# T2E.net
KiCad netlist of a schematic drawn in EAGLE
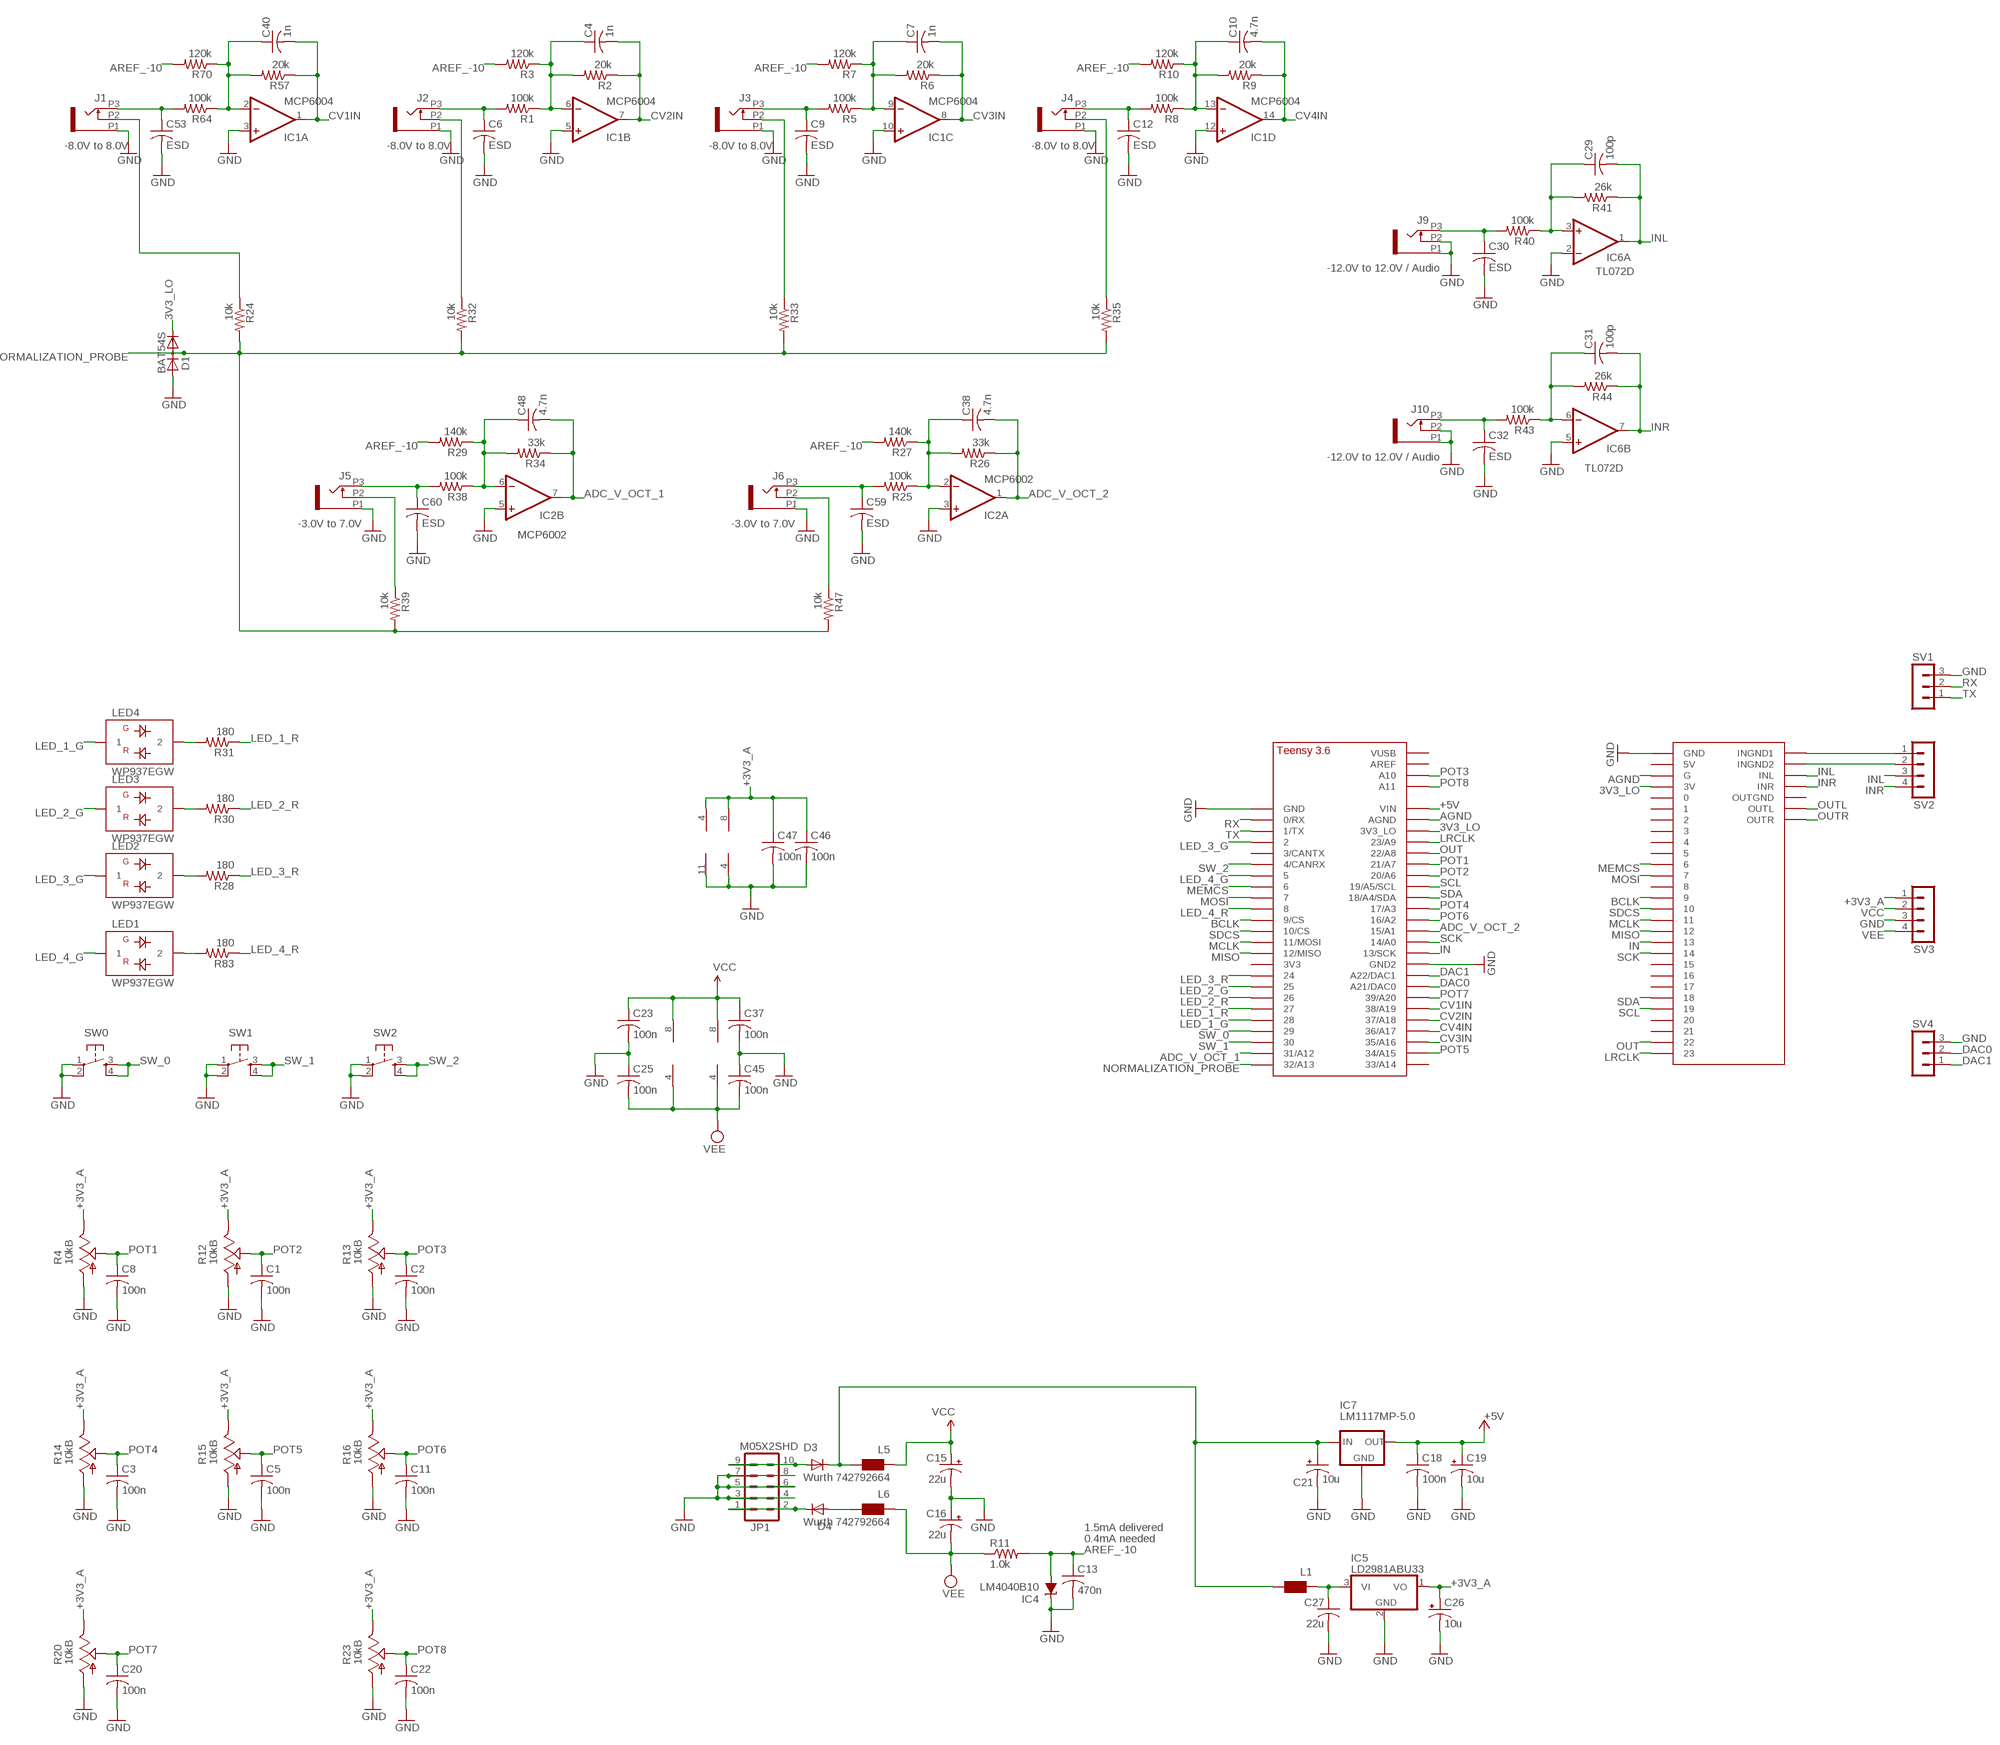
[diagram p0: schematic, sheet 1, part 1 of 2]
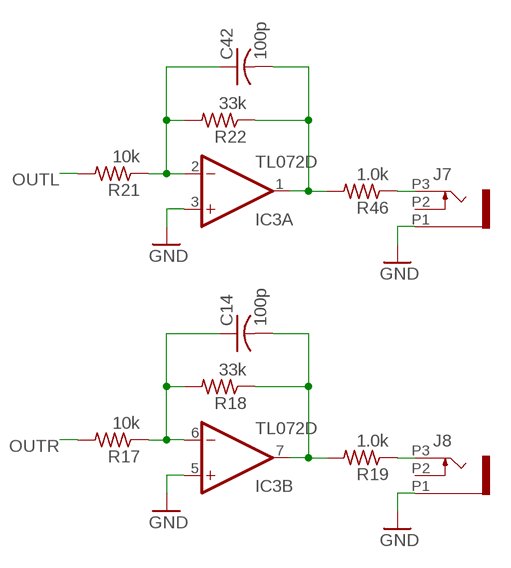
[diagram p1: schematic, sheet 1, part 2 of 2]

(export (version "E")
  (design (tool "Eeschema 10.0.6"))
  (components
    (comp (ref "C1")
      (value "100n")
      (footprint "eagle-import:C0603")
      (libsource (lib "eagle-import") (part "C-USC0603"))
    )
    (comp (ref "C2")
      (value "100n")
      (footprint "eagle-import:C0603")
      (libsource (lib "eagle-import") (part "C-USC0603"))
    )
    (comp (ref "C3")
      (value "100n")
      (footprint "eagle-import:C0603")
      (libsource (lib "eagle-import") (part "C-USC0603"))
    )
    (comp (ref "C4")
      (value "1n")
      (footprint "eagle-import:C0603")
      (libsource (lib "eagle-import") (part "C-USC0603"))
    )
    (comp (ref "C5")
      (value "100n")
      (footprint "eagle-import:C0603")
      (libsource (lib "eagle-import") (part "C-USC0603"))
    )
    (comp (ref "C6")
      (value "ESD")
      (footprint "eagle-import:C0603")
      (libsource (lib "eagle-import") (part "C-USC0603"))
    )
    (comp (ref "C7")
      (value "1n")
      (footprint "eagle-import:C0603")
      (libsource (lib "eagle-import") (part "C-USC0603"))
    )
    (comp (ref "C8")
      (value "100n")
      (footprint "eagle-import:C0603")
      (libsource (lib "eagle-import") (part "C-USC0603"))
    )
    (comp (ref "C9")
      (value "ESD")
      (footprint "eagle-import:C0603")
      (libsource (lib "eagle-import") (part "C-USC0603"))
    )
    (comp (ref "C10")
      (value "4.7n")
      (footprint "eagle-import:C0603")
      (libsource (lib "eagle-import") (part "C-USC0603"))
    )
    (comp (ref "C11")
      (value "100n")
      (footprint "eagle-import:C0603")
      (libsource (lib "eagle-import") (part "C-USC0603"))
    )
    (comp (ref "C12")
      (value "ESD")
      (footprint "eagle-import:C0603")
      (libsource (lib "eagle-import") (part "C-USC0603"))
    )
    (comp (ref "C13")
      (value "470n")
      (footprint "eagle-import:C0603")
      (libsource (lib "eagle-import") (part "C-USC0603"))
    )
    (comp (ref "C14")
      (value "100p")
      (footprint "eagle-import:C0603")
      (libsource (lib "eagle-import") (part "C-USC0603"))
    )
    (comp (ref "C15")
      (value "22u")
      (footprint "eagle-import:PANASONIC_C")
      (libsource (lib "eagle-import") (part "CPOL-USC"))
    )
    (comp (ref "C16")
      (value "22u")
      (footprint "eagle-import:PANASONIC_C")
      (libsource (lib "eagle-import") (part "CPOL-USC"))
    )
    (comp (ref "C18")
      (value "100n")
      (footprint "eagle-import:C0603")
      (libsource (lib "eagle-import") (part "C-USC0603"))
    )
    (comp (ref "C19")
      (value "10u")
      (footprint "eagle-import:PANASONIC_C")
      (libsource (lib "eagle-import") (part "CPOL-USC"))
    )
    (comp (ref "C20")
      (value "100n")
      (footprint "eagle-import:C0603")
      (libsource (lib "eagle-import") (part "C-USC0603"))
    )
    (comp (ref "C21")
      (value "10u")
      (footprint "eagle-import:PANASONIC_C")
      (libsource (lib "eagle-import") (part "CPOL-USC"))
    )
    (comp (ref "C22")
      (value "100n")
      (footprint "eagle-import:C0603")
      (libsource (lib "eagle-import") (part "C-USC0603"))
    )
    (comp (ref "C23")
      (value "100n")
      (footprint "eagle-import:C0603")
      (libsource (lib "eagle-import") (part "C-USC0603"))
    )
    (comp (ref "C25")
      (value "100n")
      (footprint "eagle-import:C0603")
      (libsource (lib "eagle-import") (part "C-USC0603"))
    )
    (comp (ref "C26")
      (value "10u")
      (footprint "eagle-import:PANASONIC_A")
      (libsource (lib "eagle-import") (part "CPOL-USA"))
    )
    (comp (ref "C27")
      (value "22u")
      (footprint "eagle-import:C1206")
      (libsource (lib "eagle-import") (part "C-USC1206"))
    )
    (comp (ref "C29")
      (value "100p")
      (footprint "eagle-import:C0603")
      (libsource (lib "eagle-import") (part "C-USC0603"))
    )
    (comp (ref "C30")
      (value "ESD")
      (footprint "eagle-import:C0603")
      (libsource (lib "eagle-import") (part "C-USC0603"))
    )
    (comp (ref "C31")
      (value "100p")
      (footprint "eagle-import:C0603")
      (libsource (lib "eagle-import") (part "C-USC0603"))
    )
    (comp (ref "C32")
      (value "ESD")
      (footprint "eagle-import:C0603")
      (libsource (lib "eagle-import") (part "C-USC0603"))
    )
    (comp (ref "C37")
      (value "100n")
      (footprint "eagle-import:C0603")
      (libsource (lib "eagle-import") (part "C-USC0603"))
    )
    (comp (ref "C38")
      (value "4.7n")
      (footprint "eagle-import:C0603")
      (libsource (lib "eagle-import") (part "C-USC0603"))
    )
    (comp (ref "C40")
      (value "1n")
      (footprint "eagle-import:C0603")
      (libsource (lib "eagle-import") (part "C-USC0603"))
    )
    (comp (ref "C42")
      (value "100p")
      (footprint "eagle-import:C0603")
      (libsource (lib "eagle-import") (part "C-USC0603"))
    )
    (comp (ref "C45")
      (value "100n")
      (footprint "eagle-import:C0603")
      (libsource (lib "eagle-import") (part "C-USC0603"))
    )
    (comp (ref "C46")
      (value "100n")
      (footprint "eagle-import:C0603")
      (libsource (lib "eagle-import") (part "C-USC0603"))
    )
    (comp (ref "C47")
      (value "100n")
      (footprint "eagle-import:C0603")
      (libsource (lib "eagle-import") (part "C-USC0603"))
    )
    (comp (ref "C48")
      (value "4.7n")
      (footprint "eagle-import:C0603")
      (libsource (lib "eagle-import") (part "C-USC0603"))
    )
    (comp (ref "C53")
      (value "ESD")
      (footprint "eagle-import:C0603")
      (libsource (lib "eagle-import") (part "C-USC0603"))
    )
    (comp (ref "C59")
      (value "ESD")
      (footprint "eagle-import:C0603")
      (libsource (lib "eagle-import") (part "C-USC0603"))
    )
    (comp (ref "C60")
      (value "ESD")
      (footprint "eagle-import:C0603")
      (libsource (lib "eagle-import") (part "C-USC0603"))
    )
    (comp (ref "D1")
      (value "BAT54S")
      (footprint "eagle-import:SOT23")
      (libsource (lib "eagle-import") (part "DIODE_2CACA-SOT23"))
    )
    (comp (ref "D3")
      (value "1N5819HW")
      (footprint "eagle-import:SOD123")
      (libsource (lib "eagle-import") (part "DIODE-SOD123"))
    )
    (comp (ref "D4")
      (value "1N5819HW")
      (footprint "eagle-import:SOD123")
      (libsource (lib "eagle-import") (part "DIODE-SOD123"))
    )
    (comp (ref "IC1")
      (value "MCP6004")
      (footprint "eagle-import:SO14")
      (libsource (lib "eagle-import") (part "TL074D"))
    )
    (comp (ref "IC2")
      (value "MCP6002")
      (footprint "eagle-import:SO08")
      (libsource (lib "eagle-import") (part "TL072D"))
    )
    (comp (ref "IC3")
      (value "TL072D")
      (footprint "eagle-import:SO08")
      (libsource (lib "eagle-import") (part "TL072D"))
    )
    (comp (ref "IC4")
      (value "LM4040B10")
      (footprint "eagle-import:DBZ_R-PDSO-G3")
      (libsource (lib "eagle-import") (part "LM4041DBZB12"))
    )
    (comp (ref "IC5")
      (value "LD2981ABU33")
      (footprint "eagle-import:SOT89")
      (libsource (lib "eagle-import") (part "LD2981ABU"))
    )
    (comp (ref "IC6")
      (value "TL072D")
      (footprint "eagle-import:SO08")
      (libsource (lib "eagle-import") (part "TL072D"))
    )
    (comp (ref "IC7")
      (value "LM1117MP-5.0")
      (footprint "eagle-import:SOT223")
      (fields (field (name "MF") "Texas Instruments"))
      (libsource (lib "eagle-import") (part "LM1117?-MP5.0"))
    )
    (comp (ref "J1")
      (value "PJ301_THONKICONN6")
      (footprint "eagle-import:WQP_PJ_301M6")
      (libsource (lib "eagle-import") (part "PJ301_THONKICONN6"))
    )
    (comp (ref "J2")
      (value "PJ301_THONKICONN6")
      (footprint "eagle-import:WQP_PJ_301M6")
      (libsource (lib "eagle-import") (part "PJ301_THONKICONN6"))
    )
    (comp (ref "J3")
      (value "PJ301_THONKICONN6")
      (footprint "eagle-import:WQP_PJ_301M6")
      (libsource (lib "eagle-import") (part "PJ301_THONKICONN6"))
    )
    (comp (ref "J4")
      (value "PJ301_THONKICONN6")
      (footprint "eagle-import:WQP_PJ_301M6")
      (libsource (lib "eagle-import") (part "PJ301_THONKICONN6"))
    )
    (comp (ref "J5")
      (value "PJ301_THONKICONN6")
      (footprint "eagle-import:WQP_PJ_301M6")
      (libsource (lib "eagle-import") (part "og-pj301_variations_PJ301_THONKICONN6"))
    )
    (comp (ref "J6")
      (value "PJ301_THONKICONN6")
      (footprint "eagle-import:WQP_PJ_301M6")
      (libsource (lib "eagle-import") (part "og-pj301_variations_PJ301_THONKICONN6"))
    )
    (comp (ref "J7")
      (value "PJ301_THONKICONN6")
      (footprint "eagle-import:WQP_PJ_301M6")
      (libsource (lib "eagle-import") (part "og-pj301_variations_PJ301_THONKICONN6"))
    )
    (comp (ref "J8")
      (value "PJ301_THONKICONN6")
      (footprint "eagle-import:WQP_PJ_301M6")
      (libsource (lib "eagle-import") (part "og-pj301_variations_PJ301_THONKICONN6"))
    )
    (comp (ref "J9")
      (value "PJ301_THONKICONN6")
      (footprint "eagle-import:WQP_PJ_301M6")
      (libsource (lib "eagle-import") (part "PJ301_THONKICONN6"))
    )
    (comp (ref "J10")
      (value "PJ301_THONKICONN6")
      (footprint "eagle-import:WQP_PJ_301M6")
      (libsource (lib "eagle-import") (part "PJ301_THONKICONN6"))
    )
    (comp (ref "JP1")
      (value "M05X2SHD")
      (footprint "eagle-import:2X5-SHROUDED")
      (libsource (lib "eagle-import") (part "M05X2SHD"))
    )
    (comp (ref "L1")
      (value "WE-CBF_0603")
      (footprint "eagle-import:0603")
      (libsource (lib "eagle-import") (part "WE-CBF_0603"))
    )
    (comp (ref "L5")
      (value "Wurth 742792664")
      (footprint "eagle-import:0603")
      (libsource (lib "eagle-import") (part "WE-CBF_0603"))
    )
    (comp (ref "L6")
      (value "Wurth 742792664")
      (footprint "eagle-import:0603")
      (libsource (lib "eagle-import") (part "WE-CBF_0603"))
    )
    (comp (ref "LED1")
      (value "WP937EGW")
      (footprint "eagle-import:LED3MM")
      (libsource (lib "eagle-import") (part "LED-BICOLOR-SHARED-THROUGHHOLE"))
    )
    (comp (ref "LED2")
      (value "WP937EGW")
      (footprint "eagle-import:LED3MM")
      (libsource (lib "eagle-import") (part "LED-BICOLOR-SHARED-THROUGHHOLE"))
    )
    (comp (ref "LED3")
      (value "WP937EGW")
      (footprint "eagle-import:LED3MM")
      (libsource (lib "eagle-import") (part "LED-BICOLOR-SHARED-THROUGHHOLE"))
    )
    (comp (ref "LED4")
      (value "WP937EGW")
      (footprint "eagle-import:LED3MM")
      (libsource (lib "eagle-import") (part "LED-BICOLOR-SHARED-THROUGHHOLE"))
    )
    (comp (ref "R1")
      (value "100k")
      (footprint "eagle-import:R0603")
      (libsource (lib "eagle-import") (part "R-US_R0603"))
    )
    (comp (ref "R2")
      (value "20k")
      (footprint "eagle-import:R0603")
      (libsource (lib "eagle-import") (part "R-US_R0603"))
    )
    (comp (ref "R3")
      (value "120k")
      (footprint "eagle-import:R0603")
      (libsource (lib "eagle-import") (part "R-US_R0603"))
    )
    (comp (ref "R4")
      (value "10kB")
      (footprint "eagle-import:ALPS_POT_VERTICAL_PS")
      (libsource (lib "eagle-import") (part "POT_USVERTICAL_PS"))
    )
    (comp (ref "R5")
      (value "100k")
      (footprint "eagle-import:R0603")
      (libsource (lib "eagle-import") (part "R-US_R0603"))
    )
    (comp (ref "R6")
      (value "20k")
      (footprint "eagle-import:R0603")
      (libsource (lib "eagle-import") (part "R-US_R0603"))
    )
    (comp (ref "R7")
      (value "120k")
      (footprint "eagle-import:R0603")
      (libsource (lib "eagle-import") (part "R-US_R0603"))
    )
    (comp (ref "R8")
      (value "100k")
      (footprint "eagle-import:R0603")
      (libsource (lib "eagle-import") (part "R-US_R0603"))
    )
    (comp (ref "R9")
      (value "20k")
      (footprint "eagle-import:R0603")
      (libsource (lib "eagle-import") (part "R-US_R0603"))
    )
    (comp (ref "R10")
      (value "120k")
      (footprint "eagle-import:R0603")
      (libsource (lib "eagle-import") (part "R-US_R0603"))
    )
    (comp (ref "R11")
      (value "1.0k")
      (footprint "eagle-import:R0603")
      (libsource (lib "eagle-import") (part "R-US_R0603"))
    )
    (comp (ref "R12")
      (value "10kB")
      (footprint "eagle-import:ALPS_POT_VERTICAL_PS")
      (libsource (lib "eagle-import") (part "POT_USVERTICAL_PS"))
    )
    (comp (ref "R13")
      (value "10kB")
      (footprint "eagle-import:ALPS_POT_VERTICAL_PS")
      (libsource (lib "eagle-import") (part "POT_USVERTICAL_PS"))
    )
    (comp (ref "R14")
      (value "10kB")
      (footprint "eagle-import:ALPS_POT_VERTICAL_PS")
      (libsource (lib "eagle-import") (part "POT_USVERTICAL_PS"))
    )
    (comp (ref "R15")
      (value "10kB")
      (footprint "eagle-import:ALPS_POT_VERTICAL_PS")
      (libsource (lib "eagle-import") (part "POT_USVERTICAL_PS"))
    )
    (comp (ref "R16")
      (value "10kB")
      (footprint "eagle-import:ALPS_POT_VERTICAL_PS")
      (libsource (lib "eagle-import") (part "POT_USVERTICAL_PS"))
    )
    (comp (ref "R17")
      (value "10k")
      (footprint "eagle-import:R0603")
      (libsource (lib "eagle-import") (part "R-US_R0603"))
    )
    (comp (ref "R18")
      (value "33k")
      (footprint "eagle-import:R0603")
      (libsource (lib "eagle-import") (part "R-US_R0603"))
    )
    (comp (ref "R19")
      (value "1.0k")
      (footprint "eagle-import:R0603")
      (libsource (lib "eagle-import") (part "R-US_R0603"))
    )
    (comp (ref "R20")
      (value "10kB")
      (footprint "eagle-import:ALPS_POT_VERTICAL_PS")
      (libsource (lib "eagle-import") (part "POT_USVERTICAL_PS"))
    )
    (comp (ref "R21")
      (value "10k")
      (footprint "eagle-import:R0603")
      (libsource (lib "eagle-import") (part "R-US_R0603"))
    )
    (comp (ref "R22")
      (value "33k")
      (footprint "eagle-import:R0603")
      (libsource (lib "eagle-import") (part "R-US_R0603"))
    )
    (comp (ref "R23")
      (value "10kB")
      (footprint "eagle-import:ALPS_POT_VERTICAL_PS")
      (libsource (lib "eagle-import") (part "POT_USVERTICAL_PS"))
    )
    (comp (ref "R24")
      (value "10k")
      (footprint "eagle-import:R0603")
      (libsource (lib "eagle-import") (part "R-US_R0603"))
    )
    (comp (ref "R25")
      (value "100k")
      (footprint "eagle-import:R0603")
      (libsource (lib "eagle-import") (part "R-US_R0603"))
    )
    (comp (ref "R26")
      (value "33k")
      (footprint "eagle-import:R0603")
      (libsource (lib "eagle-import") (part "R-US_R0603"))
    )
    (comp (ref "R27")
      (value "140k")
      (footprint "eagle-import:R0603")
      (libsource (lib "eagle-import") (part "R-US_R0603"))
    )
    (comp (ref "R28")
      (value "180")
      (footprint "eagle-import:R0603")
      (libsource (lib "eagle-import") (part "R-US_R0603"))
    )
    (comp (ref "R29")
      (value "140k")
      (footprint "eagle-import:R0603")
      (libsource (lib "eagle-import") (part "R-US_R0603"))
    )
    (comp (ref "R30")
      (value "180")
      (footprint "eagle-import:R0603")
      (libsource (lib "eagle-import") (part "R-US_R0603"))
    )
    (comp (ref "R31")
      (value "180")
      (footprint "eagle-import:R0603")
      (libsource (lib "eagle-import") (part "R-US_R0603"))
    )
    (comp (ref "R32")
      (value "10k")
      (footprint "eagle-import:R0603")
      (libsource (lib "eagle-import") (part "R-US_R0603"))
    )
    (comp (ref "R33")
      (value "10k")
      (footprint "eagle-import:R0603")
      (libsource (lib "eagle-import") (part "R-US_R0603"))
    )
    (comp (ref "R34")
      (value "33k")
      (footprint "eagle-import:R0603")
      (libsource (lib "eagle-import") (part "R-US_R0603"))
    )
    (comp (ref "R35")
      (value "10k")
      (footprint "eagle-import:R0603")
      (libsource (lib "eagle-import") (part "R-US_R0603"))
    )
    (comp (ref "R38")
      (value "100k")
      (footprint "eagle-import:R0603")
      (libsource (lib "eagle-import") (part "R-US_R0603"))
    )
    (comp (ref "R39")
      (value "10k")
      (footprint "eagle-import:R0603")
      (libsource (lib "eagle-import") (part "R-US_R0603"))
    )
    (comp (ref "R40")
      (value "100k")
      (footprint "eagle-import:R0603")
      (libsource (lib "eagle-import") (part "R-US_R0603"))
    )
    (comp (ref "R41")
      (value "26k")
      (footprint "eagle-import:R0603")
      (libsource (lib "eagle-import") (part "R-US_R0603"))
    )
    (comp (ref "R43")
      (value "100k")
      (footprint "eagle-import:R0603")
      (libsource (lib "eagle-import") (part "R-US_R0603"))
    )
    (comp (ref "R44")
      (value "26k")
      (footprint "eagle-import:R0603")
      (libsource (lib "eagle-import") (part "R-US_R0603"))
    )
    (comp (ref "R46")
      (value "1.0k")
      (footprint "eagle-import:R0603")
      (libsource (lib "eagle-import") (part "R-US_R0603"))
    )
    (comp (ref "R47")
      (value "10k")
      (footprint "eagle-import:R0603")
      (libsource (lib "eagle-import") (part "R-US_R0603"))
    )
    (comp (ref "R57")
      (value "20k")
      (footprint "eagle-import:R0603")
      (libsource (lib "eagle-import") (part "R-US_R0603"))
    )
    (comp (ref "R64")
      (value "100k")
      (footprint "eagle-import:R0603")
      (libsource (lib "eagle-import") (part "R-US_R0603"))
    )
    (comp (ref "R70")
      (value "120k")
      (footprint "eagle-import:R0603")
      (libsource (lib "eagle-import") (part "R-US_R0603"))
    )
    (comp (ref "R83")
      (value "180")
      (footprint "eagle-import:R0603")
      (libsource (lib "eagle-import") (part "R-US_R0603"))
    )
    (comp (ref "SV1")
      (value "MA03-1")
      (footprint "eagle-import:MA03-1")
      (libsource (lib "eagle-import") (part "MA03-1"))
    )
    (comp (ref "SV2")
      (value "MA04-1")
      (footprint "eagle-import:MA04-1")
      (libsource (lib "eagle-import") (part "MA04-1"))
    )
    (comp (ref "SV3")
      (value "MA04-1")
      (footprint "eagle-import:MA04-1")
      (libsource (lib "eagle-import") (part "MA04-1"))
    )
    (comp (ref "SV4")
      (value "MA03-1")
      (footprint "eagle-import:MA03-1")
      (libsource (lib "eagle-import") (part "MA03-1"))
    )
    (comp (ref "SW0")
      (value "TAC_SWITCHPTH")
      (footprint "eagle-import:TACTILE-PTH")
      (libsource (lib "eagle-import") (part "TAC_SWITCHPTH"))
    )
    (comp (ref "SW1")
      (value "TAC_SWITCHPTH")
      (footprint "eagle-import:TACTILE-PTH")
      (libsource (lib "eagle-import") (part "TAC_SWITCHPTH"))
    )
    (comp (ref "SW2")
      (value "TAC_SWITCHPTH")
      (footprint "eagle-import:TACTILE-PTH")
      (libsource (lib "eagle-import") (part "TAC_SWITCHPTH"))
    )
    (comp (ref "U$1")
      (value "TeensyAudioShield Rev C.")
      (footprint "eagle-import:AUDIOSHIELD")
      (libsource (lib "eagle-import") (part "AUDIOSHIELD"))
    )
    (comp (ref "U$4")
      (value "TEENSY_3.5/3.6_BASIC")
      (footprint "eagle-import:TEENSY_3.5_3.6_BASIC")
      (libsource (lib "eagle-import") (part "TEENSY_3.5/3.6_BASIC"))
    )
  )
  (nets
    (net (code "1") (name "+5V") (class "Default")
      (node (ref "C18") (pin "1") (pinfunction "1_1") (pintype "passive"))
      (node (ref "C19") (pin "+") (pinfunction "+_+") (pintype "passive"))
      (node (ref "IC7") (pin "2") (pinfunction "OUT_2") (pintype "passive"))
      (node (ref "IC7") (pin "4") (pinfunction "OUT_4") (pintype "passive"))
      (node (ref "U$4") (pin "VIN") (pinfunction "VIN_VIN") (pintype "bidirectional"))
    )
    (net (code "2") (name "/+3V3_A") (class "Default")
      (node (ref "C26") (pin "+") (pinfunction "+_+") (pintype "passive"))
      (node (ref "C46") (pin "1") (pinfunction "1_1") (pintype "passive"))
      (node (ref "C47") (pin "1") (pinfunction "1_1") (pintype "passive"))
      (node (ref "IC1") (pin "4") (pinfunction "V+_4") (pintype "power_in"))
      (node (ref "IC2") (pin "8") (pinfunction "V+_8") (pintype "power_in"))
      (node (ref "IC5") (pin "1") (pinfunction "VO_1") (pintype "passive"))
      (node (ref "R12") (pin "P$1") (pinfunction "E_P$1") (pintype "passive"))
      (node (ref "R13") (pin "P$1") (pinfunction "E_P$1") (pintype "passive"))
      (node (ref "R14") (pin "P$1") (pinfunction "E_P$1") (pintype "passive"))
      (node (ref "R15") (pin "P$1") (pinfunction "E_P$1") (pintype "passive"))
      (node (ref "R16") (pin "P$1") (pinfunction "E_P$1") (pintype "passive"))
      (node (ref "R20") (pin "P$1") (pinfunction "E_P$1") (pintype "passive"))
      (node (ref "R23") (pin "P$1") (pinfunction "E_P$1") (pintype "passive"))
      (node (ref "R4") (pin "P$1") (pinfunction "E_P$1") (pintype "passive"))
      (node (ref "SV3") (pin "1") (pinfunction "1_1") (pintype "passive"))
    )
    (net (code "3") (name "/3V3_LO") (class "Default")
      (node (ref "D1") (pin "2") (pinfunction "C_2") (pintype "passive"))
      (node (ref "U$1") (pin "3V") (pinfunction "3V_3V") (pintype "bidirectional"))
      (node (ref "U$4") (pin "3V3_LO") (pinfunction "3V3_LO_3V3_LO") (pintype "bidirectional"))
    )
    (net (code "4") (name "/ADC_V_OCT_1") (class "Default")
      (node (ref "C48") (pin "2") (pinfunction "2_2") (pintype "passive"))
      (node (ref "IC2") (pin "7") (pinfunction "OUT_7") (pintype "output"))
      (node (ref "R34") (pin "1") (pinfunction "1_1") (pintype "passive"))
      (node (ref "U$4") (pin "31/A12") (pinfunction "31/A12_31/A12") (pintype "bidirectional"))
    )
    (net (code "5") (name "/ADC_V_OCT_2") (class "Default")
      (node (ref "C38") (pin "2") (pinfunction "2_2") (pintype "passive"))
      (node (ref "IC2") (pin "1") (pinfunction "OUT_1") (pintype "output"))
      (node (ref "R26") (pin "1") (pinfunction "1_1") (pintype "passive"))
      (node (ref "U$4") (pin "15/A1") (pinfunction "15/A1_15/A1") (pintype "bidirectional"))
    )
    (net (code "6") (name "/AGND") (class "Default")
      (node (ref "U$1") (pin "G") (pinfunction "G_G") (pintype "bidirectional"))
      (node (ref "U$4") (pin "AGND") (pinfunction "AGND_AGND") (pintype "bidirectional"))
    )
    (net (code "7") (name "/AREF_-10") (class "Default")
      (node (ref "C13") (pin "1") (pinfunction "1_1") (pintype "passive"))
      (node (ref "IC4") (pin "2") (pinfunction "A_2") (pintype "passive"))
      (node (ref "R10") (pin "2") (pinfunction "2_2") (pintype "passive"))
      (node (ref "R11") (pin "2") (pinfunction "2_2") (pintype "passive"))
      (node (ref "R27") (pin "2") (pinfunction "2_2") (pintype "passive"))
      (node (ref "R29") (pin "2") (pinfunction "2_2") (pintype "passive"))
      (node (ref "R3") (pin "2") (pinfunction "2_2") (pintype "passive"))
      (node (ref "R7") (pin "2") (pinfunction "2_2") (pintype "passive"))
      (node (ref "R70") (pin "2") (pinfunction "2_2") (pintype "passive"))
    )
    (net (code "8") (name "/BCLK") (class "Default")
      (node (ref "U$1") (pin "9") (pinfunction "9_9") (pintype "bidirectional"))
      (node (ref "U$4") (pin "9/CS") (pinfunction "9/CS_9/CS") (pintype "bidirectional"))
    )
    (net (code "9") (name "/CV1IN") (class "Default")
      (node (ref "C40") (pin "2") (pinfunction "2_2") (pintype "passive"))
      (node (ref "IC1") (pin "1") (pinfunction "OUT_1") (pintype "output"))
      (node (ref "R57") (pin "1") (pinfunction "1_1") (pintype "passive"))
      (node (ref "U$4") (pin "38/A19") (pinfunction "38/A19_38/A19") (pintype "bidirectional"))
    )
    (net (code "10") (name "/CV2IN") (class "Default")
      (node (ref "C4") (pin "2") (pinfunction "2_2") (pintype "passive"))
      (node (ref "IC1") (pin "7") (pinfunction "OUT_7") (pintype "output"))
      (node (ref "R2") (pin "1") (pinfunction "1_1") (pintype "passive"))
      (node (ref "U$4") (pin "37/A18") (pinfunction "37/A18_37/A18") (pintype "bidirectional"))
    )
    (net (code "11") (name "/CV3IN") (class "Default")
      (node (ref "C7") (pin "2") (pinfunction "2_2") (pintype "passive"))
      (node (ref "IC1") (pin "8") (pinfunction "OUT_8") (pintype "output"))
      (node (ref "R6") (pin "1") (pinfunction "1_1") (pintype "passive"))
      (node (ref "U$4") (pin "35/A16") (pinfunction "35/A16_35/A16") (pintype "bidirectional"))
    )
    (net (code "12") (name "/CV4IN") (class "Default")
      (node (ref "C10") (pin "2") (pinfunction "2_2") (pintype "passive"))
      (node (ref "IC1") (pin "14") (pinfunction "OUT_14") (pintype "output"))
      (node (ref "R9") (pin "1") (pinfunction "1_1") (pintype "passive"))
      (node (ref "U$4") (pin "36/A17") (pinfunction "36/A17_36/A17") (pintype "bidirectional"))
    )
    (net (code "13") (name "/DAC0") (class "Default")
      (node (ref "SV4") (pin "2") (pinfunction "2_2") (pintype "passive"))
      (node (ref "U$4") (pin "21/DAC0") (pinfunction "A21/DAC0_21/DAC0") (pintype "bidirectional"))
    )
    (net (code "14") (name "/DAC1") (class "Default")
      (node (ref "SV4") (pin "1") (pinfunction "1_1") (pintype "passive"))
      (node (ref "U$4") (pin "A22/DAC1") (pinfunction "A22/DAC1_A22/DAC1") (pintype "bidirectional"))
    )
    (net (code "15") (name "/IN") (class "Default")
      (node (ref "U$1") (pin "13") (pinfunction "13_13") (pintype "bidirectional"))
      (node (ref "U$4") (pin "13/SCK") (pinfunction "13/SCK_13/SCK") (pintype "bidirectional"))
    )
    (net (code "16") (name "/INL") (class "Default")
      (node (ref "C29") (pin "2") (pinfunction "2_2") (pintype "passive"))
      (node (ref "IC6") (pin "1") (pinfunction "OUT_1") (pintype "output"))
      (node (ref "R41") (pin "1") (pinfunction "1_1") (pintype "passive"))
      (node (ref "SV2") (pin "3") (pinfunction "3_3") (pintype "passive"))
      (node (ref "U$1") (pin "INL") (pinfunction "INL_INL") (pintype "input"))
    )
    (net (code "17") (name "/INR") (class "Default")
      (node (ref "C31") (pin "2") (pinfunction "2_2") (pintype "passive"))
      (node (ref "IC6") (pin "7") (pinfunction "OUT_7") (pintype "output"))
      (node (ref "R44") (pin "1") (pinfunction "1_1") (pintype "passive"))
      (node (ref "SV2") (pin "4") (pinfunction "4_4") (pintype "passive"))
      (node (ref "U$1") (pin "INR") (pinfunction "INR_INR") (pintype "input"))
    )
    (net (code "18") (name "/LED_1_G") (class "Default")
      (node (ref "LED4") (pin "1") (pinfunction "1_1") (pintype "bidirectional"))
      (node (ref "U$4") (pin "28") (pinfunction "28_28") (pintype "bidirectional"))
    )
    (net (code "19") (name "/LED_1_R") (class "Default")
      (node (ref "R31") (pin "1") (pinfunction "1_1") (pintype "passive"))
      (node (ref "U$4") (pin "27") (pinfunction "27_27") (pintype "bidirectional"))
    )
    (net (code "20") (name "/LED_2_G") (class "Default")
      (node (ref "LED3") (pin "1") (pinfunction "1_1") (pintype "bidirectional"))
      (node (ref "U$4") (pin "25") (pinfunction "25_25") (pintype "bidirectional"))
    )
    (net (code "21") (name "/LED_2_R") (class "Default")
      (node (ref "R30") (pin "1") (pinfunction "1_1") (pintype "passive"))
      (node (ref "U$4") (pin "26") (pinfunction "26_26") (pintype "bidirectional"))
    )
    (net (code "22") (name "/LED_3_G") (class "Default")
      (node (ref "LED2") (pin "1") (pinfunction "1_1") (pintype "bidirectional"))
      (node (ref "U$4") (pin "2") (pinfunction "2_2") (pintype "bidirectional"))
    )
    (net (code "23") (name "/LED_3_R") (class "Default")
      (node (ref "R28") (pin "1") (pinfunction "1_1") (pintype "passive"))
      (node (ref "U$4") (pin "24") (pinfunction "24_24") (pintype "bidirectional"))
    )
    (net (code "24") (name "/LED_4_G") (class "Default")
      (node (ref "LED1") (pin "1") (pinfunction "1_1") (pintype "bidirectional"))
      (node (ref "U$4") (pin "5") (pinfunction "5_5") (pintype "bidirectional"))
    )
    (net (code "25") (name "/LED_4_R") (class "Default")
      (node (ref "R83") (pin "1") (pinfunction "1_1") (pintype "passive"))
      (node (ref "U$4") (pin "8") (pinfunction "8_8") (pintype "bidirectional"))
    )
    (net (code "26") (name "/LRCLK") (class "Default")
      (node (ref "U$1") (pin "23") (pinfunction "23_23") (pintype "bidirectional"))
      (node (ref "U$4") (pin "23/A9") (pinfunction "23/A9_23/A9") (pintype "bidirectional"))
    )
    (net (code "27") (name "/MCLK") (class "Default")
      (node (ref "U$1") (pin "11") (pinfunction "11_11") (pintype "bidirectional"))
      (node (ref "U$4") (pin "11/MOSI") (pinfunction "11/MOSI_11/MOSI") (pintype "bidirectional"))
    )
    (net (code "28") (name "/MEMCS") (class "Default")
      (node (ref "U$1") (pin "6") (pinfunction "6_6") (pintype "bidirectional"))
      (node (ref "U$4") (pin "6") (pinfunction "6_6") (pintype "bidirectional"))
    )
    (net (code "29") (name "/MISO") (class "Default")
      (node (ref "U$1") (pin "12") (pinfunction "12_12") (pintype "bidirectional"))
      (node (ref "U$4") (pin "12/MISO") (pinfunction "12/MISO_12/MISO") (pintype "bidirectional"))
    )
    (net (code "30") (name "/MOSI") (class "Default")
      (node (ref "U$1") (pin "7") (pinfunction "7_7") (pintype "bidirectional"))
      (node (ref "U$4") (pin "7") (pinfunction "7_7") (pintype "bidirectional"))
    )
    (net (code "31") (name "/NORMALIZATION_PROBE") (class "Default")
      (node (ref "D1") (pin "3") (pinfunction "AC_3") (pintype "passive"))
      (node (ref "R24") (pin "2") (pinfunction "2_2") (pintype "passive"))
      (node (ref "R32") (pin "2") (pinfunction "2_2") (pintype "passive"))
      (node (ref "R33") (pin "2") (pinfunction "2_2") (pintype "passive"))
      (node (ref "R35") (pin "2") (pinfunction "2_2") (pintype "passive"))
      (node (ref "R39") (pin "2") (pinfunction "2_2") (pintype "passive"))
      (node (ref "R47") (pin "2") (pinfunction "2_2") (pintype "passive"))
      (node (ref "U$4") (pin "32/A13") (pinfunction "32/A13_32/A13") (pintype "bidirectional"))
    )
    (net (code "32") (name "/OUT") (class "Default")
      (node (ref "U$1") (pin "22") (pinfunction "22_22") (pintype "bidirectional"))
      (node (ref "U$4") (pin "22/A8") (pinfunction "22/A8_22/A8") (pintype "bidirectional"))
    )
    (net (code "33") (name "/OUTL") (class "Default")
      (node (ref "R21") (pin "2") (pinfunction "2_2") (pintype "passive"))
      (node (ref "U$1") (pin "OUTL") (pinfunction "OUTL_OUTL") (pintype "output"))
    )
    (net (code "34") (name "/OUTR") (class "Default")
      (node (ref "R17") (pin "2") (pinfunction "2_2") (pintype "passive"))
      (node (ref "U$1") (pin "OUTR") (pinfunction "OUTR_OUTR") (pintype "output"))
    )
    (net (code "35") (name "/POT1") (class "Default")
      (node (ref "C8") (pin "1") (pinfunction "1_1") (pintype "passive"))
      (node (ref "R4") (pin "P$2") (pinfunction "S_P$2") (pintype "passive"))
      (node (ref "U$4") (pin "21/A7") (pinfunction "21/A7_21/A7") (pintype "bidirectional"))
    )
    (net (code "36") (name "/POT2") (class "Default")
      (node (ref "C1") (pin "1") (pinfunction "1_1") (pintype "passive"))
      (node (ref "R12") (pin "P$2") (pinfunction "S_P$2") (pintype "passive"))
      (node (ref "U$4") (pin "20/A6") (pinfunction "20/A6_20/A6") (pintype "bidirectional"))
    )
    (net (code "37") (name "/POT3") (class "Default")
      (node (ref "C2") (pin "1") (pinfunction "1_1") (pintype "passive"))
      (node (ref "R13") (pin "P$2") (pinfunction "S_P$2") (pintype "passive"))
      (node (ref "U$4") (pin "A10") (pinfunction "A10_A10") (pintype "bidirectional"))
    )
    (net (code "38") (name "/POT4") (class "Default")
      (node (ref "C3") (pin "1") (pinfunction "1_1") (pintype "passive"))
      (node (ref "R14") (pin "P$2") (pinfunction "S_P$2") (pintype "passive"))
      (node (ref "U$4") (pin "17/A3") (pinfunction "17/A3_17/A3") (pintype "bidirectional"))
    )
    (net (code "39") (name "/POT5") (class "Default")
      (node (ref "C5") (pin "1") (pinfunction "1_1") (pintype "passive"))
      (node (ref "R15") (pin "P$2") (pinfunction "S_P$2") (pintype "passive"))
      (node (ref "U$4") (pin "34/A15") (pinfunction "34/A15_34/A15") (pintype "bidirectional"))
    )
    (net (code "40") (name "/POT6") (class "Default")
      (node (ref "C11") (pin "1") (pinfunction "1_1") (pintype "passive"))
      (node (ref "R16") (pin "P$2") (pinfunction "S_P$2") (pintype "passive"))
      (node (ref "U$4") (pin "16/A2") (pinfunction "16/A2_16/A2") (pintype "bidirectional"))
    )
    (net (code "41") (name "/POT7") (class "Default")
      (node (ref "C20") (pin "1") (pinfunction "1_1") (pintype "passive"))
      (node (ref "R20") (pin "P$2") (pinfunction "S_P$2") (pintype "passive"))
      (node (ref "U$4") (pin "39/A20") (pinfunction "39/A20_39/A20") (pintype "bidirectional"))
    )
    (net (code "42") (name "/POT8") (class "Default")
      (node (ref "C22") (pin "1") (pinfunction "1_1") (pintype "passive"))
      (node (ref "R23") (pin "P$2") (pinfunction "S_P$2") (pintype "passive"))
      (node (ref "U$4") (pin "A11") (pinfunction "A11_A11") (pintype "bidirectional"))
    )
    (net (code "43") (name "/RX") (class "Default")
      (node (ref "SV1") (pin "2") (pinfunction "2_2") (pintype "passive"))
      (node (ref "U$4") (pin "0/RX") (pinfunction "0/RX_0/RX") (pintype "bidirectional"))
    )
    (net (code "44") (name "/SCK") (class "Default")
      (node (ref "U$1") (pin "14") (pinfunction "14_14") (pintype "bidirectional"))
      (node (ref "U$4") (pin "14/A0") (pinfunction "14/A0_14/A0") (pintype "bidirectional"))
    )
    (net (code "45") (name "/SCL") (class "Default")
      (node (ref "U$1") (pin "19") (pinfunction "19_19") (pintype "bidirectional"))
      (node (ref "U$4") (pin "19/A5/SCL") (pinfunction "19/A5/SCL_19/A5/SCL") (pintype "bidirectional"))
    )
    (net (code "46") (name "/SDA") (class "Default")
      (node (ref "U$1") (pin "18") (pinfunction "18_18") (pintype "bidirectional"))
      (node (ref "U$4") (pin "18/A4/SDA") (pinfunction "18/A4/SDA_18/A4/SDA") (pintype "bidirectional"))
    )
    (net (code "47") (name "/SDCS") (class "Default")
      (node (ref "U$1") (pin "10") (pinfunction "10_10") (pintype "bidirectional"))
      (node (ref "U$4") (pin "10/CS") (pinfunction "10/CS_10/CS") (pintype "bidirectional"))
    )
    (net (code "48") (name "/SW_0") (class "Default")
      (node (ref "SW0") (pin "3") (pinfunction "3_3") (pintype "passive"))
      (node (ref "SW0") (pin "4") (pinfunction "4_4") (pintype "passive"))
      (node (ref "U$4") (pin "29") (pinfunction "29_29") (pintype "bidirectional"))
    )
    (net (code "49") (name "/SW_1") (class "Default")
      (node (ref "SW1") (pin "3") (pinfunction "3_3") (pintype "passive"))
      (node (ref "SW1") (pin "4") (pinfunction "4_4") (pintype "passive"))
      (node (ref "U$4") (pin "30") (pinfunction "30_30") (pintype "bidirectional"))
    )
    (net (code "50") (name "/SW_2") (class "Default")
      (node (ref "SW2") (pin "3") (pinfunction "3_3") (pintype "passive"))
      (node (ref "SW2") (pin "4") (pinfunction "4_4") (pintype "passive"))
      (node (ref "U$4") (pin "4/CANRX") (pinfunction "4/CANRX_4/CANRX") (pintype "bidirectional"))
    )
    (net (code "51") (name "/TX") (class "Default")
      (node (ref "SV1") (pin "1") (pinfunction "1_1") (pintype "passive"))
      (node (ref "U$4") (pin "1/TX") (pinfunction "1/TX_1/TX") (pintype "bidirectional"))
    )
    (net (code "52") (name "GND") (class "Default")
      (node (ref "C1") (pin "2") (pinfunction "2_2") (pintype "passive"))
      (node (ref "C11") (pin "2") (pinfunction "2_2") (pintype "passive"))
      (node (ref "C12") (pin "2") (pinfunction "2_2") (pintype "passive"))
      (node (ref "C13") (pin "2") (pinfunction "2_2") (pintype "passive"))
      (node (ref "C15") (pin "-") (pinfunction "-_-") (pintype "passive"))
      (node (ref "C16") (pin "+") (pinfunction "+_+") (pintype "passive"))
      (node (ref "C18") (pin "2") (pinfunction "2_2") (pintype "passive"))
      (node (ref "C19") (pin "-") (pinfunction "-_-") (pintype "passive"))
      (node (ref "C2") (pin "2") (pinfunction "2_2") (pintype "passive"))
      (node (ref "C20") (pin "2") (pinfunction "2_2") (pintype "passive"))
      (node (ref "C21") (pin "-") (pinfunction "-_-") (pintype "passive"))
      (node (ref "C22") (pin "2") (pinfunction "2_2") (pintype "passive"))
      (node (ref "C23") (pin "2") (pinfunction "2_2") (pintype "passive"))
      (node (ref "C25") (pin "1") (pinfunction "1_1") (pintype "passive"))
      (node (ref "C26") (pin "-") (pinfunction "-_-") (pintype "passive"))
      (node (ref "C27") (pin "2") (pinfunction "2_2") (pintype "passive"))
      (node (ref "C3") (pin "2") (pinfunction "2_2") (pintype "passive"))
      (node (ref "C30") (pin "2") (pinfunction "2_2") (pintype "passive"))
      (node (ref "C32") (pin "2") (pinfunction "2_2") (pintype "passive"))
      (node (ref "C37") (pin "2") (pinfunction "2_2") (pintype "passive"))
      (node (ref "C45") (pin "1") (pinfunction "1_1") (pintype "passive"))
      (node (ref "C46") (pin "2") (pinfunction "2_2") (pintype "passive"))
      (node (ref "C47") (pin "2") (pinfunction "2_2") (pintype "passive"))
      (node (ref "C5") (pin "2") (pinfunction "2_2") (pintype "passive"))
      (node (ref "C53") (pin "2") (pinfunction "2_2") (pintype "passive"))
      (node (ref "C59") (pin "2") (pinfunction "2_2") (pintype "passive"))
      (node (ref "C6") (pin "2") (pinfunction "2_2") (pintype "passive"))
      (node (ref "C60") (pin "2") (pinfunction "2_2") (pintype "passive"))
      (node (ref "C8") (pin "2") (pinfunction "2_2") (pintype "passive"))
      (node (ref "C9") (pin "2") (pinfunction "2_2") (pintype "passive"))
      (node (ref "D1") (pin "1") (pinfunction "A_1") (pintype "passive"))
      (node (ref "IC1") (pin "10") (pinfunction "+IN_10") (pintype "input"))
      (node (ref "IC1") (pin "11") (pinfunction "V-_11") (pintype "power_in"))
      (node (ref "IC1") (pin "12") (pinfunction "+IN_12") (pintype "input"))
      (node (ref "IC1") (pin "3") (pinfunction "+IN_3") (pintype "input"))
      (node (ref "IC1") (pin "5") (pinfunction "+IN_5") (pintype "input"))
      (node (ref "IC2") (pin "3") (pinfunction "+IN_3") (pintype "input"))
      (node (ref "IC2") (pin "4") (pinfunction "V-_4") (pintype "power_in"))
      (node (ref "IC2") (pin "5") (pinfunction "+IN_5") (pintype "input"))
      (node (ref "IC3") (pin "3") (pinfunction "+IN_3") (pintype "input"))
      (node (ref "IC3") (pin "5") (pinfunction "+IN_5") (pintype "input"))
      (node (ref "IC4") (pin "1") (pinfunction "C_1") (pintype "passive"))
      (node (ref "IC5") (pin "2") (pinfunction "GND_2") (pintype "passive"))
      (node (ref "IC6") (pin "2") (pinfunction "-IN_2") (pintype "input"))
      (node (ref "IC6") (pin "5") (pinfunction "+IN_5") (pintype "input"))
      (node (ref "IC7") (pin "1") (pinfunction "GND_1") (pintype "input"))
      (node (ref "J1") (pin "P1") (pinfunction "1_P1") (pintype "passive"))
      (node (ref "J10") (pin "P1") (pinfunction "1_P1") (pintype "passive"))
      (node (ref "J10") (pin "P2") (pinfunction "2_P2") (pintype "passive"))
      (node (ref "J2") (pin "P1") (pinfunction "1_P1") (pintype "passive"))
      (node (ref "J3") (pin "P1") (pinfunction "1_P1") (pintype "passive"))
      (node (ref "J4") (pin "P1") (pinfunction "1_P1") (pintype "passive"))
      (node (ref "J5") (pin "P1") (pinfunction "1_P1") (pintype "passive"))
      (node (ref "J6") (pin "P1") (pinfunction "1_P1") (pintype "passive"))
      (node (ref "J7") (pin "P1") (pinfunction "1_P1") (pintype "passive"))
      (node (ref "J8") (pin "P1") (pinfunction "1_P1") (pintype "passive"))
      (node (ref "J9") (pin "P1") (pinfunction "1_P1") (pintype "passive"))
      (node (ref "J9") (pin "P2") (pinfunction "2_P2") (pintype "passive"))
      (node (ref "JP1") (pin "3") (pinfunction "3_3") (pintype "passive"))
      (node (ref "JP1") (pin "4") (pinfunction "4_4") (pintype "passive"))
      (node (ref "JP1") (pin "5") (pinfunction "5_5") (pintype "passive"))
      (node (ref "JP1") (pin "6") (pinfunction "6_6") (pintype "passive"))
      (node (ref "JP1") (pin "7") (pinfunction "7_7") (pintype "passive"))
      (node (ref "JP1") (pin "8") (pinfunction "8_8") (pintype "passive"))
      (node (ref "R12") (pin "P$3") (pinfunction "A_P$3") (pintype "passive"))
      (node (ref "R13") (pin "P$3") (pinfunction "A_P$3") (pintype "passive"))
      (node (ref "R14") (pin "P$3") (pinfunction "A_P$3") (pintype "passive"))
      (node (ref "R15") (pin "P$3") (pinfunction "A_P$3") (pintype "passive"))
      (node (ref "R16") (pin "P$3") (pinfunction "A_P$3") (pintype "passive"))
      (node (ref "R20") (pin "P$3") (pinfunction "A_P$3") (pintype "passive"))
      (node (ref "R23") (pin "P$3") (pinfunction "A_P$3") (pintype "passive"))
      (node (ref "R4") (pin "P$3") (pinfunction "A_P$3") (pintype "passive"))
      (node (ref "SV1") (pin "3") (pinfunction "3_3") (pintype "passive"))
      (node (ref "SV3") (pin "3") (pinfunction "3_3") (pintype "passive"))
      (node (ref "SV4") (pin "3") (pinfunction "3_3") (pintype "passive"))
      (node (ref "SW0") (pin "1") (pinfunction "1_1") (pintype "passive"))
      (node (ref "SW0") (pin "2") (pinfunction "2_2") (pintype "passive"))
      (node (ref "SW1") (pin "1") (pinfunction "1_1") (pintype "passive"))
      (node (ref "SW1") (pin "2") (pinfunction "2_2") (pintype "passive"))
      (node (ref "SW2") (pin "1") (pinfunction "1_1") (pintype "passive"))
      (node (ref "SW2") (pin "2") (pinfunction "2_2") (pintype "passive"))
      (node (ref "U$1") (pin "GND") (pinfunction "GND_GND") (pintype "bidirectional"))
      (node (ref "U$4") (pin "GND") (pinfunction "GND_GND") (pintype "bidirectional"))
      (node (ref "U$4") (pin "GND2") (pinfunction "GND2_GND2") (pintype "bidirectional"))
    )
    (net (code "53") (name "Net-(D3-PadA)") (class "Default")
      (node (ref "D3") (pin "A") (pinfunction "A_A") (pintype "passive"))
      (node (ref "JP1") (pin "10") (pinfunction "10_10") (pintype "passive"))
      (node (ref "JP1") (pin "9") (pinfunction "9_9") (pintype "passive"))
    )
    (net (code "54") (name "Net-(D4-PadA)") (class "Default")
      (node (ref "D4") (pin "A") (pinfunction "A_A") (pintype "passive"))
      (node (ref "L6") (pin "2") (pinfunction "2_2") (pintype "passive"))
    )
    (net (code "55") (name "Net-(D4-PadC)") (class "Default")
      (node (ref "D4") (pin "C") (pinfunction "C_C") (pintype "passive"))
      (node (ref "JP1") (pin "1") (pinfunction "1_1") (pintype "passive"))
      (node (ref "JP1") (pin "2") (pinfunction "2_2") (pintype "passive"))
    )
    (net (code "56") (name "Net-(IC1A--IN)") (class "Default")
      (node (ref "C40") (pin "1") (pinfunction "1_1") (pintype "passive"))
      (node (ref "IC1") (pin "2") (pinfunction "-IN_2") (pintype "input"))
      (node (ref "R57") (pin "2") (pinfunction "2_2") (pintype "passive"))
      (node (ref "R64") (pin "1") (pinfunction "1_1") (pintype "passive"))
      (node (ref "R70") (pin "1") (pinfunction "1_1") (pintype "passive"))
    )
    (net (code "57") (name "Net-(IC1B--IN)") (class "Default")
      (node (ref "C4") (pin "1") (pinfunction "1_1") (pintype "passive"))
      (node (ref "IC1") (pin "6") (pinfunction "-IN_6") (pintype "input"))
      (node (ref "R1") (pin "1") (pinfunction "1_1") (pintype "passive"))
      (node (ref "R2") (pin "2") (pinfunction "2_2") (pintype "passive"))
      (node (ref "R3") (pin "1") (pinfunction "1_1") (pintype "passive"))
    )
    (net (code "58") (name "Net-(IC1C--IN)") (class "Default")
      (node (ref "C7") (pin "1") (pinfunction "1_1") (pintype "passive"))
      (node (ref "IC1") (pin "9") (pinfunction "-IN_9") (pintype "input"))
      (node (ref "R5") (pin "1") (pinfunction "1_1") (pintype "passive"))
      (node (ref "R6") (pin "2") (pinfunction "2_2") (pintype "passive"))
      (node (ref "R7") (pin "1") (pinfunction "1_1") (pintype "passive"))
    )
    (net (code "59") (name "Net-(IC1D--IN)") (class "Default")
      (node (ref "C10") (pin "1") (pinfunction "1_1") (pintype "passive"))
      (node (ref "IC1") (pin "13") (pinfunction "-IN_13") (pintype "input"))
      (node (ref "R10") (pin "1") (pinfunction "1_1") (pintype "passive"))
      (node (ref "R8") (pin "1") (pinfunction "1_1") (pintype "passive"))
      (node (ref "R9") (pin "2") (pinfunction "2_2") (pintype "passive"))
    )
    (net (code "60") (name "Net-(IC2A--IN)") (class "Default")
      (node (ref "C38") (pin "1") (pinfunction "1_1") (pintype "passive"))
      (node (ref "IC2") (pin "2") (pinfunction "-IN_2") (pintype "input"))
      (node (ref "R25") (pin "1") (pinfunction "1_1") (pintype "passive"))
      (node (ref "R26") (pin "2") (pinfunction "2_2") (pintype "passive"))
      (node (ref "R27") (pin "1") (pinfunction "1_1") (pintype "passive"))
    )
    (net (code "61") (name "Net-(IC2B--IN)") (class "Default")
      (node (ref "C48") (pin "1") (pinfunction "1_1") (pintype "passive"))
      (node (ref "IC2") (pin "6") (pinfunction "-IN_6") (pintype "input"))
      (node (ref "R29") (pin "1") (pinfunction "1_1") (pintype "passive"))
      (node (ref "R34") (pin "2") (pinfunction "2_2") (pintype "passive"))
      (node (ref "R38") (pin "1") (pinfunction "1_1") (pintype "passive"))
    )
    (net (code "62") (name "Net-(IC3A--IN)") (class "Default")
      (node (ref "C42") (pin "1") (pinfunction "1_1") (pintype "passive"))
      (node (ref "IC3") (pin "2") (pinfunction "-IN_2") (pintype "input"))
      (node (ref "R21") (pin "1") (pinfunction "1_1") (pintype "passive"))
      (node (ref "R22") (pin "2") (pinfunction "2_2") (pintype "passive"))
    )
    (net (code "63") (name "Net-(IC3A-OUT)") (class "Default")
      (node (ref "C42") (pin "2") (pinfunction "2_2") (pintype "passive"))
      (node (ref "IC3") (pin "1") (pinfunction "OUT_1") (pintype "output"))
      (node (ref "R22") (pin "1") (pinfunction "1_1") (pintype "passive"))
      (node (ref "R46") (pin "2") (pinfunction "2_2") (pintype "passive"))
    )
    (net (code "64") (name "Net-(IC3B--IN)") (class "Default")
      (node (ref "C14") (pin "1") (pinfunction "1_1") (pintype "passive"))
      (node (ref "IC3") (pin "6") (pinfunction "-IN_6") (pintype "input"))
      (node (ref "R17") (pin "1") (pinfunction "1_1") (pintype "passive"))
      (node (ref "R18") (pin "2") (pinfunction "2_2") (pintype "passive"))
    )
    (net (code "65") (name "Net-(IC3B-OUT)") (class "Default")
      (node (ref "C14") (pin "2") (pinfunction "2_2") (pintype "passive"))
      (node (ref "IC3") (pin "7") (pinfunction "OUT_7") (pintype "output"))
      (node (ref "R18") (pin "1") (pinfunction "1_1") (pintype "passive"))
      (node (ref "R19") (pin "2") (pinfunction "2_2") (pintype "passive"))
    )
    (net (code "66") (name "Net-(IC5-VI)") (class "Default")
      (node (ref "C27") (pin "1") (pinfunction "1_1") (pintype "passive"))
      (node (ref "IC5") (pin "3") (pinfunction "VI_3") (pintype "input"))
      (node (ref "L1") (pin "1") (pinfunction "1_1") (pintype "passive"))
    )
    (net (code "67") (name "Net-(IC6A-+IN)") (class "Default")
      (node (ref "C29") (pin "1") (pinfunction "1_1") (pintype "passive"))
      (node (ref "IC6") (pin "3") (pinfunction "+IN_3") (pintype "input"))
      (node (ref "R40") (pin "1") (pinfunction "1_1") (pintype "passive"))
      (node (ref "R41") (pin "2") (pinfunction "2_2") (pintype "passive"))
    )
    (net (code "68") (name "Net-(IC6B--IN)") (class "Default")
      (node (ref "C31") (pin "1") (pinfunction "1_1") (pintype "passive"))
      (node (ref "IC6") (pin "6") (pinfunction "-IN_6") (pintype "input"))
      (node (ref "R43") (pin "1") (pinfunction "1_1") (pintype "passive"))
      (node (ref "R44") (pin "2") (pinfunction "2_2") (pintype "passive"))
    )
    (net (code "69") (name "Net-(IC7-IN)") (class "Default")
      (node (ref "C21") (pin "+") (pinfunction "+_+") (pintype "passive"))
      (node (ref "D3") (pin "C") (pinfunction "C_C") (pintype "passive"))
      (node (ref "IC7") (pin "3") (pinfunction "IN_3") (pintype "input"))
      (node (ref "L1") (pin "2") (pinfunction "2_2") (pintype "passive"))
      (node (ref "L5") (pin "2") (pinfunction "2_2") (pintype "passive"))
    )
    (net (code "70") (name "Net-(J1-2)") (class "Default")
      (node (ref "J1") (pin "P2") (pinfunction "2_P2") (pintype "passive"))
      (node (ref "R24") (pin "1") (pinfunction "1_1") (pintype "passive"))
    )
    (net (code "71") (name "Net-(J1-3)") (class "Default")
      (node (ref "C53") (pin "1") (pinfunction "1_1") (pintype "passive"))
      (node (ref "J1") (pin "P3") (pinfunction "3_P3") (pintype "passive"))
      (node (ref "R64") (pin "2") (pinfunction "2_2") (pintype "passive"))
    )
    (net (code "72") (name "Net-(J2-2)") (class "Default")
      (node (ref "J2") (pin "P2") (pinfunction "2_P2") (pintype "passive"))
      (node (ref "R32") (pin "1") (pinfunction "1_1") (pintype "passive"))
    )
    (net (code "73") (name "Net-(J2-3)") (class "Default")
      (node (ref "C6") (pin "1") (pinfunction "1_1") (pintype "passive"))
      (node (ref "J2") (pin "P3") (pinfunction "3_P3") (pintype "passive"))
      (node (ref "R1") (pin "2") (pinfunction "2_2") (pintype "passive"))
    )
    (net (code "74") (name "Net-(J3-2)") (class "Default")
      (node (ref "J3") (pin "P2") (pinfunction "2_P2") (pintype "passive"))
      (node (ref "R33") (pin "1") (pinfunction "1_1") (pintype "passive"))
    )
    (net (code "75") (name "Net-(J3-3)") (class "Default")
      (node (ref "C9") (pin "1") (pinfunction "1_1") (pintype "passive"))
      (node (ref "J3") (pin "P3") (pinfunction "3_P3") (pintype "passive"))
      (node (ref "R5") (pin "2") (pinfunction "2_2") (pintype "passive"))
    )
    (net (code "76") (name "Net-(J4-2)") (class "Default")
      (node (ref "J4") (pin "P2") (pinfunction "2_P2") (pintype "passive"))
      (node (ref "R35") (pin "1") (pinfunction "1_1") (pintype "passive"))
    )
    (net (code "77") (name "Net-(J4-3)") (class "Default")
      (node (ref "C12") (pin "1") (pinfunction "1_1") (pintype "passive"))
      (node (ref "J4") (pin "P3") (pinfunction "3_P3") (pintype "passive"))
      (node (ref "R8") (pin "2") (pinfunction "2_2") (pintype "passive"))
    )
    (net (code "78") (name "Net-(J5-2)") (class "Default")
      (node (ref "J5") (pin "P2") (pinfunction "2_P2") (pintype "passive"))
      (node (ref "R39") (pin "1") (pinfunction "1_1") (pintype "passive"))
    )
    (net (code "79") (name "Net-(J5-3)") (class "Default")
      (node (ref "C60") (pin "1") (pinfunction "1_1") (pintype "passive"))
      (node (ref "J5") (pin "P3") (pinfunction "3_P3") (pintype "passive"))
      (node (ref "R38") (pin "2") (pinfunction "2_2") (pintype "passive"))
    )
    (net (code "80") (name "Net-(J6-2)") (class "Default")
      (node (ref "J6") (pin "P2") (pinfunction "2_P2") (pintype "passive"))
      (node (ref "R47") (pin "1") (pinfunction "1_1") (pintype "passive"))
    )
    (net (code "81") (name "Net-(J6-3)") (class "Default")
      (node (ref "C59") (pin "1") (pinfunction "1_1") (pintype "passive"))
      (node (ref "J6") (pin "P3") (pinfunction "3_P3") (pintype "passive"))
      (node (ref "R25") (pin "2") (pinfunction "2_2") (pintype "passive"))
    )
    (net (code "82") (name "Net-(J7-3)") (class "Default")
      (node (ref "J7") (pin "P3") (pinfunction "3_P3") (pintype "passive"))
      (node (ref "R46") (pin "1") (pinfunction "1_1") (pintype "passive"))
    )
    (net (code "83") (name "Net-(J8-3)") (class "Default")
      (node (ref "J8") (pin "P3") (pinfunction "3_P3") (pintype "passive"))
      (node (ref "R19") (pin "1") (pinfunction "1_1") (pintype "passive"))
    )
    (net (code "84") (name "Net-(J9-3)") (class "Default")
      (node (ref "C30") (pin "1") (pinfunction "1_1") (pintype "passive"))
      (node (ref "J9") (pin "P3") (pinfunction "3_P3") (pintype "passive"))
      (node (ref "R40") (pin "2") (pinfunction "2_2") (pintype "passive"))
    )
    (net (code "85") (name "Net-(J10-3)") (class "Default")
      (node (ref "C32") (pin "1") (pinfunction "1_1") (pintype "passive"))
      (node (ref "J10") (pin "P3") (pinfunction "3_P3") (pintype "passive"))
      (node (ref "R43") (pin "2") (pinfunction "2_2") (pintype "passive"))
    )
    (net (code "86") (name "Net-(LED1-Pad2)") (class "Default")
      (node (ref "LED1") (pin "2") (pinfunction "2_2") (pintype "bidirectional"))
      (node (ref "R83") (pin "2") (pinfunction "2_2") (pintype "passive"))
    )
    (net (code "87") (name "Net-(LED2-Pad2)") (class "Default")
      (node (ref "LED2") (pin "2") (pinfunction "2_2") (pintype "bidirectional"))
      (node (ref "R28") (pin "2") (pinfunction "2_2") (pintype "passive"))
    )
    (net (code "88") (name "Net-(LED3-Pad2)") (class "Default")
      (node (ref "LED3") (pin "2") (pinfunction "2_2") (pintype "bidirectional"))
      (node (ref "R30") (pin "2") (pinfunction "2_2") (pintype "passive"))
    )
    (net (code "89") (name "Net-(LED4-Pad2)") (class "Default")
      (node (ref "LED4") (pin "2") (pinfunction "2_2") (pintype "bidirectional"))
      (node (ref "R31") (pin "2") (pinfunction "2_2") (pintype "passive"))
    )
    (net (code "90") (name "Net-(SV2-Pad1)") (class "Default")
      (node (ref "SV2") (pin "1") (pinfunction "1_1") (pintype "passive"))
      (node (ref "U$1") (pin "INGND1") (pinfunction "INGND1_INGND1") (pintype "bidirectional"))
    )
    (net (code "91") (name "Net-(SV2-Pad2)") (class "Default")
      (node (ref "SV2") (pin "2") (pinfunction "2_2") (pintype "passive"))
      (node (ref "U$1") (pin "INGND2") (pinfunction "INGND2_INGND2") (pintype "bidirectional"))
    )
    (net (code "92") (name "VCC") (class "Default")
      (node (ref "C15") (pin "+") (pinfunction "+_+") (pintype "passive"))
      (node (ref "C23") (pin "1") (pinfunction "1_1") (pintype "passive"))
      (node (ref "C37") (pin "1") (pinfunction "1_1") (pintype "passive"))
      (node (ref "IC3") (pin "8") (pinfunction "V+_8") (pintype "power_in"))
      (node (ref "IC6") (pin "8") (pinfunction "V+_8") (pintype "power_in"))
      (node (ref "L5") (pin "1") (pinfunction "1_1") (pintype "passive"))
      (node (ref "SV3") (pin "2") (pinfunction "2_2") (pintype "passive"))
    )
    (net (code "93") (name "VEE") (class "Default")
      (node (ref "C16") (pin "-") (pinfunction "-_-") (pintype "passive"))
      (node (ref "C25") (pin "2") (pinfunction "2_2") (pintype "passive"))
      (node (ref "C45") (pin "2") (pinfunction "2_2") (pintype "passive"))
      (node (ref "IC3") (pin "4") (pinfunction "V-_4") (pintype "power_in"))
      (node (ref "IC6") (pin "4") (pinfunction "V-_4") (pintype "power_in"))
      (node (ref "L6") (pin "1") (pinfunction "1_1") (pintype "passive"))
      (node (ref "R11") (pin "1") (pinfunction "1_1") (pintype "passive"))
      (node (ref "SV3") (pin "4") (pinfunction "4_4") (pintype "passive"))
    )
    (net (code "94") (name "unconnected-(J7-2-PadP2)") (class "Default")
      (node (ref "J7") (pin "P2") (pinfunction "2_P2") (pintype "passive"))
    )
    (net (code "95") (name "unconnected-(J8-2-PadP2)") (class "Default")
      (node (ref "J8") (pin "P2") (pinfunction "2_P2") (pintype "passive"))
    )
    (net (code "96") (name "unconnected-(U$1-Pad0)") (class "Default")
      (node (ref "U$1") (pin "0") (pinfunction "0_0") (pintype "bidirectional"))
    )
    (net (code "97") (name "unconnected-(U$1-Pad1)") (class "Default")
      (node (ref "U$1") (pin "1") (pinfunction "1_1") (pintype "bidirectional"))
    )
    (net (code "98") (name "unconnected-(U$1-Pad2)") (class "Default")
      (node (ref "U$1") (pin "2") (pinfunction "2_2") (pintype "bidirectional"))
    )
    (net (code "99") (name "unconnected-(U$1-Pad3)") (class "Default")
      (node (ref "U$1") (pin "3") (pinfunction "3_3") (pintype "bidirectional"))
    )
    (net (code "100") (name "unconnected-(U$1-Pad4)") (class "Default")
      (node (ref "U$1") (pin "4") (pinfunction "4_4") (pintype "bidirectional"))
    )
    (net (code "101") (name "unconnected-(U$1-Pad5)") (class "Default")
      (node (ref "U$1") (pin "5") (pinfunction "5_5") (pintype "bidirectional"))
    )
    (net (code "102") (name "unconnected-(U$1-Pad5V)") (class "Default")
      (node (ref "U$1") (pin "5V") (pinfunction "5V_5V") (pintype "bidirectional"))
    )
    (net (code "103") (name "unconnected-(U$1-Pad8)") (class "Default")
      (node (ref "U$1") (pin "8") (pinfunction "8_8") (pintype "bidirectional"))
    )
    (net (code "104") (name "unconnected-(U$1-Pad15)") (class "Default")
      (node (ref "U$1") (pin "15") (pinfunction "15_15") (pintype "bidirectional"))
    )
    (net (code "105") (name "unconnected-(U$1-Pad16)") (class "Default")
      (node (ref "U$1") (pin "16") (pinfunction "16_16") (pintype "bidirectional"))
    )
    (net (code "106") (name "unconnected-(U$1-Pad17)") (class "Default")
      (node (ref "U$1") (pin "17") (pinfunction "17_17") (pintype "bidirectional"))
    )
    (net (code "107") (name "unconnected-(U$1-Pad20)") (class "Default")
      (node (ref "U$1") (pin "20") (pinfunction "20_20") (pintype "bidirectional"))
    )
    (net (code "108") (name "unconnected-(U$1-Pad21)") (class "Default")
      (node (ref "U$1") (pin "21") (pinfunction "21_21") (pintype "bidirectional"))
    )
    (net (code "109") (name "unconnected-(U$1-PadOUTGND)") (class "Default")
      (node (ref "U$1") (pin "OUTGND") (pinfunction "OUTGND_OUTGND") (pintype "bidirectional"))
    )
    (net (code "110") (name "unconnected-(U$4-Pad3V3)") (class "Default")
      (node (ref "U$4") (pin "3V3") (pinfunction "3V3_3V3") (pintype "bidirectional"))
    )
    (net (code "111") (name "unconnected-(U$4-Pad3{slash}CANTX)") (class "Default")
      (node (ref "U$4") (pin "3/CANTX") (pinfunction "3/CANTX_3/CANTX") (pintype "bidirectional"))
    )
    (net (code "112") (name "unconnected-(U$4-Pad33{slash}A14)") (class "Default")
      (node (ref "U$4") (pin "33/A14") (pinfunction "33/A14_33/A14") (pintype "bidirectional"))
    )
    (net (code "113") (name "unconnected-(U$4-PadAREF)") (class "Default")
      (node (ref "U$4") (pin "AREF") (pinfunction "AREF_AREF") (pintype "bidirectional"))
    )
    (net (code "114") (name "unconnected-(U$4-PadVUSB)") (class "Default")
      (node (ref "U$4") (pin "VUSB") (pinfunction "VUSB_VUSB") (pintype "bidirectional"))
    )
  )
)
